# 01_Power_Input.net
KiCad netlist of a schematic drawn in Altium Designer
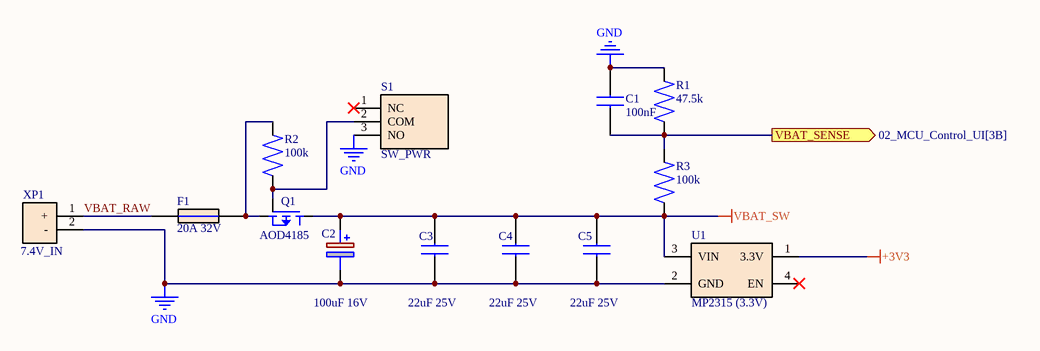
[diagram p0: 01_Power_Input.SchDoc]

(export (version "E")
  (design (tool "Eeschema 10.0.6"))
  (components
    (comp (ref "C1")
      (value "100nF")
      (footprint "CHIP_0603_SMD")
      (description "Capacitor MLCC, Ceramic, 100 nF, 50 V, ±10%, X7R, SMD 0603, Samsung Electro-Mechanics")
      (libsource (lib "Schlib1") (part "CAP_0603_100nF_50V_X7R"))
    )
    (comp (ref "C2")
      (value "100uF 16V")
      (footprint "CAP_ALU_SMD_D5.0_L5.4")
      (libsource (lib "Schlib1") (part "CAP_POLY_SMD_100uF_16V_D6.3"))
    )
    (comp (ref "C3")
      (value "22uF 25V")
      (footprint "CHIP_1210_3225")
      (description "Capacitor MLCC, Ceramic, 22 uF, 25 V, ±10%, X7R, SMD 1210, Murata Electronics")
      (libsource (lib "Schlib1") (part "CAP_1210_22uF_25V_X7R"))
    )
    (comp (ref "C4")
      (value "22uF 25V")
      (footprint "CHIP_1210_3225")
      (description "Capacitor MLCC, Ceramic, 22 uF, 25 V, ±10%, X7R, SMD 1210, Murata Electronics")
      (libsource (lib "Schlib1") (part "CAP_1210_22uF_25V_X7R"))
    )
    (comp (ref "C5")
      (value "22uF 25V")
      (footprint "CHIP_1210_3225")
      (description "Capacitor MLCC, Ceramic, 22 uF, 25 V, ±10%, X7R, SMD 1210, Murata Electronics")
      (libsource (lib "Schlib1") (part "CAP_1210_22uF_25V_X7R"))
    )
    (comp (ref "F1")
      (value "20A 32V")
      (footprint "FUSE_HOLDER_MINI_KEYSTONE_3544")
      (description "Automotive Fuse Mini Blade, 20A, 32V DC, Fast-Acting, with PCB Holder/Clips")
      (libsource (lib "Schlib1") (part "FUSE_MINI_BLADE_20A"))
    )
    (comp (ref "Q1")
      (value "AOD4185")
      (footprint "TO-252-2L_DPAK_THERMAL")
      (description "MOSFET P-Channel, -40V, -40A, 20 mOhm @ -10V, TO-252-2L (DPAK), Alpha & Omega Semiconductor")
      (libsource (lib "Schlib1") (part "MOSFET_P-CH_AOD4185"))
    )
    (comp (ref "R1")
      (value "47.5k")
      (footprint "CHIP_0603_SMD")
      (description "Resistor, 47.5 kOhm, ±1%, 0.1W (1/10W), SMD 0603, Thick Film, Yageo")
      (libsource (lib "Schlib1") (part "RES_0603_47.5k_1%"))
    )
    (comp (ref "R2")
      (value "100k")
      (footprint "CHIP_0603_SMD")
      (description "Resistor, 100 kOhm, ±1%, 0.1W (1/10W), SMD 0603, Thick Film, Yageo")
      (libsource (lib "Schlib1") (part "RES_0603_100k_1%"))
    )
    (comp (ref "R3")
      (value "100k")
      (footprint "CHIP_0603_SMD")
      (description "Resistor, 100 kOhm, ±1%, 0.1W (1/10W), SMD 0603, Thick Film, Yageo")
      (libsource (lib "Schlib1") (part "RES_0603_100k_1%"))
    )
    (comp (ref "S1")
      (value "SW_PWR")
      (footprint "TNT_SW_SLIDE_2.5mm")
      (description "Slide Switch, SPDT (1P2T), 50V DC 0.5A, Through-Hole (THT), Vertical, Actuator Height 6mm")
      (libsource (lib "Schlib1") (part "SW_SLIDE_SPDT_SS12D00"))
    )
    (comp (ref "U1")
      (value "MP2315 (3.3V)")
      (footprint "MODULE_DC-DC_MP2315_MINI_BUCK_THT")
      (description "DC-DC Step-Down Buck Converter Module, MP2315, Vin 4.5V-24V, Vout 3.3V 3A, Sub-Board PCB Mount")
      (libsource (lib "Schlib1") (part "MODULE_DC-DC_MP2315_3V3"))
    )
    (comp (ref "XP1")
      (value "7.4V_IN")
      (footprint "CONN_XT30PW-M_2P")
      (libsource (lib "Schlib1") (part "CONN_XT30PW-M_2P"))
    )
  )
  (nets
    (net (code "1") (name "+3V3") (class "Default")
      (node (ref "U1") (pin "1") (pinfunction "3.3V_1") (pintype "passive"))
    )
    (net (code "2") (name "/VBAT_RAW") (class "Default")
      (node (ref "F1") (pin "1") (pinfunction "1_1") (pintype "passive"))
      (node (ref "XP1") (pin "1") (pinfunction "+_1") (pintype "power_in"))
    )
    (net (code "3") (name "/VBAT_SENSE") (class "Default")
      (node (ref "C1") (pin "1") (pinfunction "1_1") (pintype "passive"))
      (node (ref "R1") (pin "1") (pinfunction "1_1") (pintype "passive"))
      (node (ref "R3") (pin "2") (pinfunction "2_2") (pintype "passive"))
    )
    (net (code "4") (name "GND") (class "Default")
      (node (ref "C1") (pin "2") (pinfunction "2_2") (pintype "passive"))
      (node (ref "C2") (pin "2") (pinfunction "-_2") (pintype "passive"))
      (node (ref "C3") (pin "1") (pinfunction "1_1") (pintype "passive"))
      (node (ref "C4") (pin "1") (pinfunction "1_1") (pintype "passive"))
      (node (ref "C5") (pin "1") (pinfunction "1_1") (pintype "passive"))
      (node (ref "R1") (pin "2") (pinfunction "2_2") (pintype "passive"))
      (node (ref "S1") (pin "3") (pinfunction "NO_3") (pintype "passive"))
      (node (ref "U1") (pin "2") (pinfunction "GND_2") (pintype "power_in"))
      (node (ref "XP1") (pin "2") (pinfunction "-_2") (pintype "power_in"))
    )
    (net (code "5") (name "Net-(Q1-G)") (class "Default")
      (node (ref "Q1") (pin "1") (pinfunction "G_1") (pintype "passive"))
      (node (ref "R2") (pin "1") (pinfunction "1_1") (pintype "passive"))
      (node (ref "S1") (pin "2") (pinfunction "COM_2") (pintype "passive"))
    )
    (net (code "6") (name "Net-(Q1-S)") (class "Default")
      (node (ref "F1") (pin "2") (pinfunction "2_2") (pintype "passive"))
      (node (ref "Q1") (pin "3") (pinfunction "S_3") (pintype "passive"))
      (node (ref "R2") (pin "2") (pinfunction "2_2") (pintype "passive"))
    )
    (net (code "7") (name "VBAT_SW") (class "Default")
      (node (ref "C2") (pin "1") (pinfunction "+_1") (pintype "passive"))
      (node (ref "C3") (pin "2") (pinfunction "2_2") (pintype "passive"))
      (node (ref "C4") (pin "2") (pinfunction "2_2") (pintype "passive"))
      (node (ref "C5") (pin "2") (pinfunction "2_2") (pintype "passive"))
      (node (ref "Q1") (pin "2") (pinfunction "D_2") (pintype "passive"))
      (node (ref "R3") (pin "1") (pinfunction "1_1") (pintype "passive"))
      (node (ref "U1") (pin "3") (pinfunction "VIN_3") (pintype "passive"))
    )
    (net (code "8") (name "unconnected-(S1-NC-Pad1)") (class "Default")
      (node (ref "S1") (pin "1") (pinfunction "NC_1") (pintype "passive+no_connect"))
    )
    (net (code "9") (name "unconnected-(U1-EN-Pad4)") (class "Default")
      (node (ref "U1") (pin "4") (pinfunction "EN_4") (pintype "power_in+no_connect"))
    )
  )
)
